# Driver.net
KiCad netlist of a schematic drawn in Altium Designer
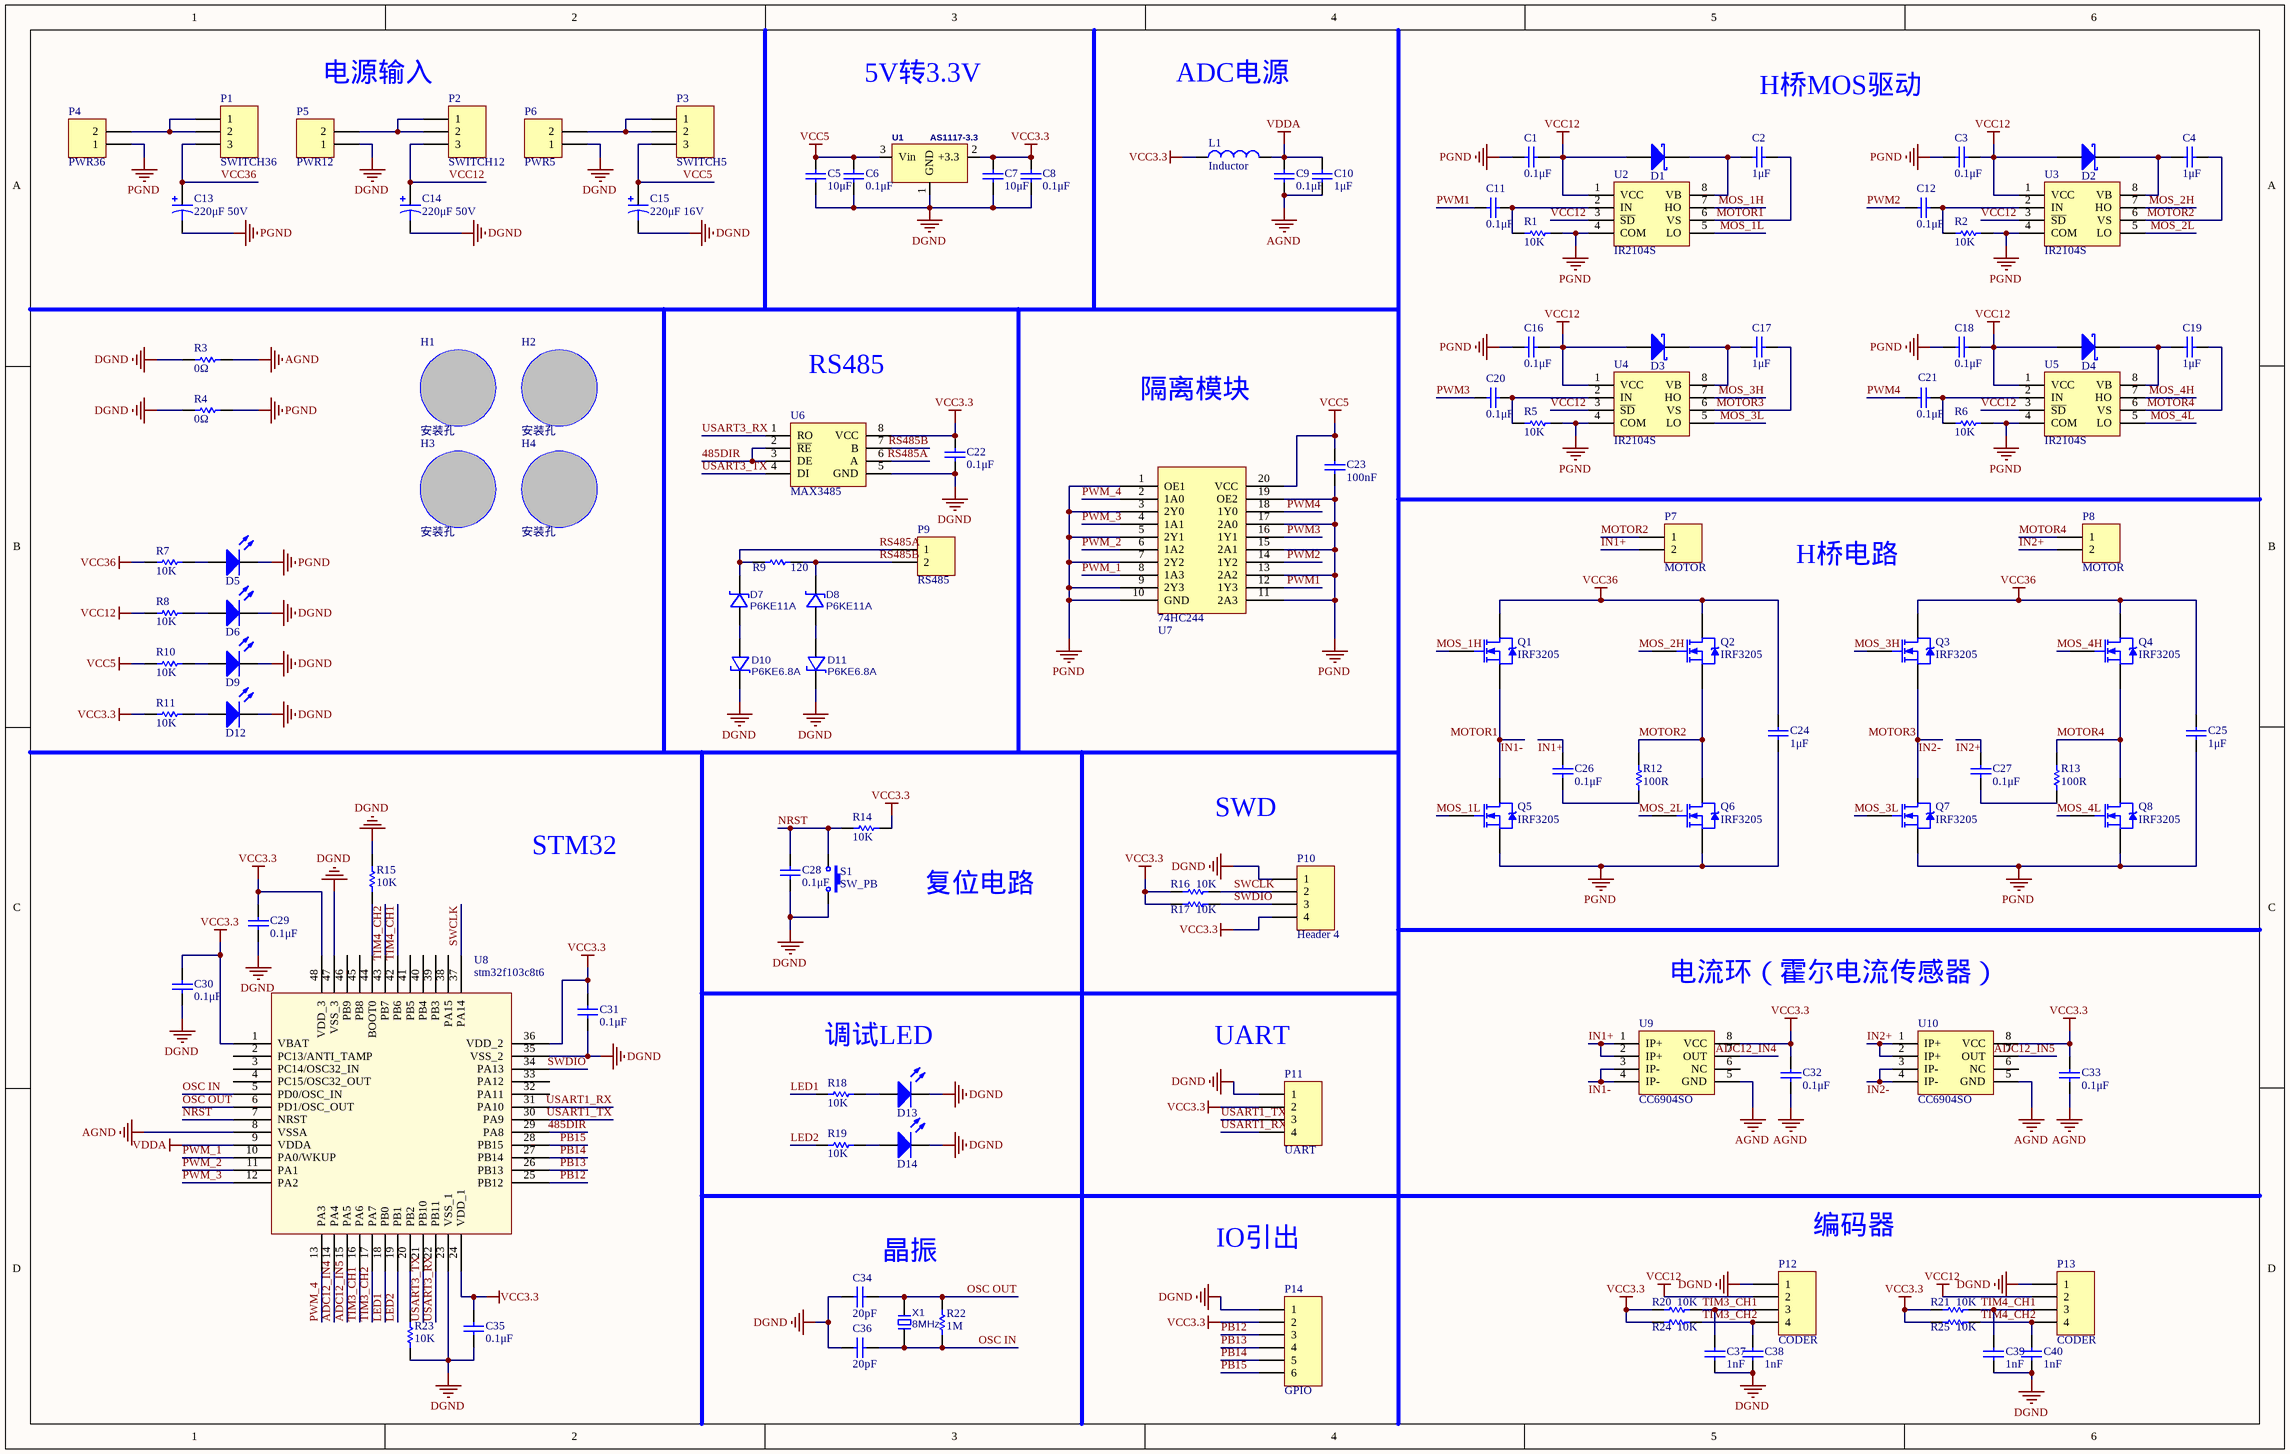
[diagram p0: Driver.SchDoc]

(export (version "E")
  (design (tool "Eeschema 10.0.6"))
  (components
    (comp (ref "C1")
      (value "0.1μF")
      (footprint "0603C")
      (description "Capacitor")
      (fields (field (name "PUBLISHER") "Altium Limited"))
      (libsource (lib "Driver") (part "Cap"))
    )
    (comp (ref "C2")
      (value "1μF")
      (footprint "0603C")
      (description "Capacitor")
      (fields (field (name "PUBLISHER") "Altium Limited"))
      (libsource (lib "Driver") (part "Cap"))
    )
    (comp (ref "C3")
      (value "0.1μF")
      (footprint "0603C")
      (description "Capacitor")
      (fields (field (name "PUBLISHER") "Altium Limited"))
      (libsource (lib "Driver") (part "Cap"))
    )
    (comp (ref "C4")
      (value "1μF")
      (footprint "0603C")
      (description "Capacitor")
      (fields (field (name "PUBLISHER") "Altium Limited"))
      (libsource (lib "Driver") (part "Cap"))
    )
    (comp (ref "C5")
      (value "10μF")
      (footprint "0603C")
      (description "Capacitor")
      (fields (field (name "PUBLISHER") "Altium Limited"))
      (libsource (lib "Driver") (part "Cap"))
    )
    (comp (ref "C6")
      (value "0.1μF")
      (footprint "0603C")
      (description "Capacitor")
      (fields (field (name "PUBLISHER") "Altium Limited"))
      (libsource (lib "Driver") (part "Cap"))
    )
    (comp (ref "C7")
      (value "10μF")
      (footprint "0603C")
      (description "Capacitor")
      (fields (field (name "PUBLISHER") "Altium Limited"))
      (libsource (lib "Driver") (part "Cap"))
    )
    (comp (ref "C8")
      (value "0.1μF")
      (footprint "0603C")
      (description "Capacitor")
      (fields (field (name "PUBLISHER") "Altium Limited"))
      (libsource (lib "Driver") (part "Cap"))
    )
    (comp (ref "C9")
      (value "0.1μF")
      (footprint "0603C")
      (description "Capacitor")
      (fields (field (name "PUBLISHER") "Altium Limited"))
      (libsource (lib "Driver") (part "Cap"))
    )
    (comp (ref "C10")
      (value "1μF")
      (footprint "0603C")
      (description "Capacitor")
      (fields (field (name "PUBLISHER") "Altium Limited"))
      (libsource (lib "Driver") (part "Cap"))
    )
    (comp (ref "C11")
      (value "0.1μF")
      (footprint "0603C")
      (description "Capacitor")
      (fields (field (name "PUBLISHER") "Altium Limited"))
      (libsource (lib "Driver") (part "Cap"))
    )
    (comp (ref "C12")
      (value "0.1μF")
      (footprint "0603C")
      (description "Capacitor")
      (fields (field (name "PUBLISHER") "Altium Limited"))
      (libsource (lib "Driver") (part "Cap"))
    )
    (comp (ref "C13")
      (value "220μF 50V")
      (footprint "CAP-TH_BD10.0-P5.00-D1.0-FD")
      (description "Capacitor")
      (libsource (lib "Driver") (part "Cap_A"))
    )
    (comp (ref "C14")
      (value "220μF 50V")
      (footprint "CAP-TH_BD10.0-P5.00-D1.0-FD")
      (description "Capacitor")
      (libsource (lib "Driver") (part "Cap_A"))
    )
    (comp (ref "C15")
      (value "220μF 16V")
      (footprint "CAP-TH_BD6.3-P2.50-D1.0-FD")
      (description "Capacitor")
      (libsource (lib "Driver") (part "Cap_A"))
    )
    (comp (ref "C16")
      (value "0.1μF")
      (footprint "0603C")
      (description "Capacitor")
      (fields (field (name "PUBLISHER") "Altium Limited"))
      (libsource (lib "Driver") (part "Cap"))
    )
    (comp (ref "C17")
      (value "1μF")
      (footprint "0603C")
      (description "Capacitor")
      (fields (field (name "PUBLISHER") "Altium Limited"))
      (libsource (lib "Driver") (part "Cap"))
    )
    (comp (ref "C18")
      (value "0.1μF")
      (footprint "0603C")
      (description "Capacitor")
      (fields (field (name "PUBLISHER") "Altium Limited"))
      (libsource (lib "Driver") (part "Cap"))
    )
    (comp (ref "C19")
      (value "1μF")
      (footprint "0603C")
      (description "Capacitor")
      (fields (field (name "PUBLISHER") "Altium Limited"))
      (libsource (lib "Driver") (part "Cap"))
    )
    (comp (ref "C20")
      (value "0.1μF")
      (footprint "0603C")
      (description "Capacitor")
      (fields (field (name "PUBLISHER") "Altium Limited"))
      (libsource (lib "Driver") (part "Cap"))
    )
    (comp (ref "C21")
      (value "0.1μF")
      (footprint "0603C")
      (description "Capacitor")
      (fields (field (name "PUBLISHER") "Altium Limited"))
      (libsource (lib "Driver") (part "Cap"))
    )
    (comp (ref "C22")
      (value "0.1μF")
      (footprint "0603C")
      (description "Capacitor")
      (fields (field (name "PUBLISHER") "Altium Limited"))
      (libsource (lib "Driver") (part "Cap"))
    )
    (comp (ref "C23")
      (value "100nF")
      (footprint "0603C")
      (description "Capacitor")
      (fields (field (name "PUBLISHER") "Altium Limited"))
      (libsource (lib "Driver") (part "Cap"))
    )
    (comp (ref "C24")
      (value "1μF")
      (footprint "C1206")
      (description "Capacitor")
      (fields (field (name "PUBLISHER") "Altium Limited"))
      (libsource (lib "Driver") (part "Cap"))
    )
    (comp (ref "C25")
      (value "1μF")
      (footprint "C1206")
      (description "Capacitor")
      (fields (field (name "PUBLISHER") "Altium Limited"))
      (libsource (lib "Driver") (part "Cap"))
    )
    (comp (ref "C26")
      (value "0.1μF")
      (footprint "0603C")
      (description "Capacitor")
      (fields (field (name "PUBLISHER") "Altium Limited"))
      (libsource (lib "Driver") (part "Cap"))
    )
    (comp (ref "C27")
      (value "0.1μF")
      (footprint "0603C")
      (description "Capacitor")
      (fields (field (name "PUBLISHER") "Altium Limited"))
      (libsource (lib "Driver") (part "Cap"))
    )
    (comp (ref "C28")
      (value "0.1μF")
      (footprint "0603C")
      (description "Capacitor")
      (fields (field (name "PUBLISHER") "Altium Limited"))
      (libsource (lib "Driver") (part "Cap"))
    )
    (comp (ref "C29")
      (value "0.1μF")
      (footprint "0603C")
      (description "Capacitor")
      (fields (field (name "PUBLISHER") "Altium Limited"))
      (libsource (lib "Driver") (part "Cap"))
    )
    (comp (ref "C30")
      (value "0.1μF")
      (footprint "0603C")
      (description "Capacitor")
      (fields (field (name "PUBLISHER") "Altium Limited"))
      (libsource (lib "Driver") (part "Cap"))
    )
    (comp (ref "C31")
      (value "0.1μF")
      (footprint "0603C")
      (description "Capacitor")
      (fields (field (name "PUBLISHER") "Altium Limited"))
      (libsource (lib "Driver") (part "Cap"))
    )
    (comp (ref "C32")
      (value "0.1μF")
      (footprint "0603C")
      (description "Capacitor")
      (fields (field (name "PUBLISHER") "Altium Limited"))
      (libsource (lib "Driver") (part "Cap"))
    )
    (comp (ref "C33")
      (value "0.1μF")
      (footprint "0603C")
      (description "Capacitor")
      (fields (field (name "PUBLISHER") "Altium Limited"))
      (libsource (lib "Driver") (part "Cap"))
    )
    (comp (ref "C34")
      (value "20pF")
      (footprint "0603C")
      (description "Capacitor")
      (fields (field (name "PUBLISHER") "Altium Limited"))
      (libsource (lib "Driver") (part "Cap"))
    )
    (comp (ref "C35")
      (value "0.1μF")
      (footprint "0603C")
      (description "Capacitor")
      (fields (field (name "PUBLISHER") "Altium Limited"))
      (libsource (lib "Driver") (part "Cap"))
    )
    (comp (ref "C36")
      (value "20pF")
      (footprint "0603C")
      (description "Capacitor")
      (fields (field (name "PUBLISHER") "Altium Limited"))
      (libsource (lib "Driver") (part "Cap"))
    )
    (comp (ref "C37")
      (value "1nF")
      (footprint "6-0805_N")
      (description "Capacitor")
      (fields (field (name "PUBLISHER") "Altium Limited"))
      (libsource (lib "") (part "Cap_1"))
    )
    (comp (ref "C38")
      (value "1nF")
      (footprint "6-0805_N")
      (description "Capacitor")
      (fields (field (name "PUBLISHER") "Altium Limited"))
      (libsource (lib "") (part "Cap_1"))
    )
    (comp (ref "C39")
      (value "1nF")
      (footprint "6-0805_N")
      (description "Capacitor")
      (fields (field (name "PUBLISHER") "Altium Limited"))
      (libsource (lib "") (part "Cap_1"))
    )
    (comp (ref "C40")
      (value "1nF")
      (footprint "6-0805_N")
      (description "Capacitor")
      (fields (field (name "PUBLISHER") "Altium Limited"))
      (libsource (lib "") (part "Cap_1"))
    )
    (comp (ref "D1")
      (value "D-SS12")
      (footprint "SMA_L4.4-W2.6-LS5.0-RD")
      (libsource (lib "Driver") (part "D-SS12"))
    )
    (comp (ref "D2")
      (value "D-SS12")
      (footprint "SMA_L4.4-W2.6-LS5.0-RD")
      (libsource (lib "Driver") (part "D-SS12"))
    )
    (comp (ref "D3")
      (value "D-SS12")
      (footprint "SMA_L4.4-W2.6-LS5.0-RD")
      (libsource (lib "Driver") (part "D-SS12"))
    )
    (comp (ref "D4")
      (value "D-SS12")
      (footprint "SMA_L4.4-W2.6-LS5.0-RD")
      (libsource (lib "Driver") (part "D-SS12"))
    )
    (comp (ref "D5") (value "LED_0603") (footprint "0603D") (libsource (lib "Driver") (part "LED_0603")))
    (comp (ref "D6") (value "LED_0603") (footprint "0603D") (libsource (lib "Driver") (part "LED_0603")))
    (comp (ref "D7")
      (value "P6KE11A")
      (footprint "SMB")
      (fields (field (name "BOM_MANUFACTURER PART") "P6KE68A") (field (name "BOM_SUPPLIER PART") "C10195"))
      (libsource (lib "Driver") (part "P6KE68A"))
    )
    (comp (ref "D8")
      (value "P6KE11A")
      (footprint "SMB")
      (fields (field (name "BOM_MANUFACTURER PART") "P6KE68A") (field (name "BOM_SUPPLIER PART") "C10195"))
      (libsource (lib "Driver") (part "P6KE68A"))
    )
    (comp (ref "D9") (value "LED_0603") (footprint "0603D") (libsource (lib "Driver") (part "LED_0603")))
    (comp (ref "D10")
      (value "P6KE6.8A")
      (footprint "SMB")
      (fields (field (name "BOM_MANUFACTURER PART") "P6KE68A") (field (name "BOM_SUPPLIER PART") "C10195"))
      (libsource (lib "Driver") (part "P6KE68A"))
    )
    (comp (ref "D11")
      (value "P6KE6.8A")
      (footprint "SMB")
      (fields (field (name "BOM_MANUFACTURER PART") "P6KE68A") (field (name "BOM_SUPPLIER PART") "C10195"))
      (libsource (lib "Driver") (part "P6KE68A"))
    )
    (comp (ref "D12") (value "LED_0603") (footprint "0603D") (libsource (lib "Driver") (part "LED_0603")))
    (comp (ref "D13") (value "LED_0603") (footprint "0603D") (libsource (lib "Driver") (part "LED_0603")))
    (comp (ref "D14") (value "LED_0603") (footprint "0603D") (libsource (lib "Driver") (part "LED_0603")))
    (comp (ref "H1") (value "安装孔") (footprint "安装孔") (libsource (lib "Driver") (part "安装孔")))
    (comp (ref "H2") (value "安装孔") (footprint "安装孔") (libsource (lib "Driver") (part "安装孔")))
    (comp (ref "H3") (value "安装孔") (footprint "安装孔") (libsource (lib "Driver") (part "安装孔")))
    (comp (ref "H4") (value "安装孔") (footprint "安装孔") (libsource (lib "Driver") (part "安装孔")))
    (comp (ref "L1") (value "Inductor") (footprint "0603L") (libsource (lib "Driver") (part "Inductor")))
    (comp (ref "P1")
      (value "SWITCH36")
      (footprint "船型开关")
      (description "Header, 3-Pin")
      (fields (field (name "PUBLISHER") "Altium Limited"))
      (libsource (lib "Miscellaneous Connectors") (part "Header 3"))
    )
    (comp (ref "P2")
      (value "SWITCH12")
      (footprint "钮子开关")
      (description "Header, 3-Pin")
      (fields (field (name "PUBLISHER") "Altium Limited"))
      (libsource (lib "Miscellaneous Connectors") (part "Header 3"))
    )
    (comp (ref "P3")
      (value "SWITCH5")
      (footprint "SWITCH_SS-12F44")
      (description "Header, 3-Pin")
      (fields (field (name "PUBLISHER") "Altium Limited"))
      (libsource (lib "Miscellaneous Connectors") (part "Header 3"))
    )
    (comp (ref "P4")
      (value "PWR36")
      (footprint "KF301")
      (description "Header, 2-Pin")
      (fields (field (name "PUBLISHER") "Altium Limited"))
      (libsource (lib "Miscellaneous Connectors") (part "Header 2"))
    )
    (comp (ref "P5")
      (value "PWR12")
      (footprint "HDR1X2")
      (description "Header, 2-Pin")
      (fields (field (name "PUBLISHER") "Altium Limited"))
      (libsource (lib "Miscellaneous Connectors") (part "Header 2"))
    )
    (comp (ref "P6")
      (value "PWR5")
      (footprint "HDR1X2")
      (description "Header, 2-Pin")
      (fields (field (name "PUBLISHER") "Altium Limited"))
      (libsource (lib "Miscellaneous Connectors") (part "Header 2"))
    )
    (comp (ref "P7")
      (value "MOTOR")
      (footprint "KF301")
      (description "Header, 2-Pin")
      (fields (field (name "PUBLISHER") "Altium Limited"))
      (libsource (lib "") (part "Header 2_1"))
    )
    (comp (ref "P8")
      (value "MOTOR")
      (footprint "KF301")
      (description "Header, 2-Pin")
      (fields (field (name "PUBLISHER") "Altium Limited"))
      (libsource (lib "") (part "Header 2_1"))
    )
    (comp (ref "P9")
      (value "RS485")
      (footprint "HDR1X2")
      (description "Header, 2-Pin")
      (fields (field (name "PUBLISHER") "Altium Limited"))
      (libsource (lib "") (part "Header 2_1"))
    )
    (comp (ref "P10")
      (value "Header 4")
      (footprint "HDR1X4")
      (description "Header, 4-Pin")
      (fields (field (name "PUBLISHER") "Altium Limited"))
      (libsource (lib "Miscellaneous Connectors") (part "Header 4"))
    )
    (comp (ref "P11")
      (value "UART")
      (footprint "HDR1X4")
      (description "Header, 4-Pin")
      (fields (field (name "PUBLISHER") "Altium Limited"))
      (libsource (lib "Miscellaneous Connectors") (part "Header 4"))
    )
    (comp (ref "P12")
      (value "CODER")
      (footprint "HDR1X4")
      (description "Header, 4-Pin")
      (fields (field (name "PUBLISHER") "Altium Limited"))
      (libsource (lib "Miscellaneous Connectors") (part "Header 4"))
    )
    (comp (ref "P13")
      (value "CODER")
      (footprint "HDR1X4")
      (description "Header, 4-Pin")
      (fields (field (name "PUBLISHER") "Altium Limited"))
      (libsource (lib "Miscellaneous Connectors") (part "Header 4"))
    )
    (comp (ref "P14")
      (value "GPIO")
      (footprint "HDR1X6")
      (description "Header, 6-Pin")
      (fields (field (name "PUBLISHER") "Altium Limited"))
      (libsource (lib "Miscellaneous Connectors") (part "Header 6"))
    )
    (comp (ref "Q1")
      (value "IRF3205")
      (footprint "IRF3205_D2PAK")
      (fields (field (name "PUBLISHER") "Altium Limited"))
      (libsource (lib "Driver") (part "IRF3205"))
    )
    (comp (ref "Q2")
      (value "IRF3205")
      (footprint "IRF3205_D2PAK")
      (fields (field (name "PUBLISHER") "Altium Limited"))
      (libsource (lib "Driver") (part "IRF3205"))
    )
    (comp (ref "Q3")
      (value "IRF3205")
      (footprint "IRF3205_D2PAK")
      (fields (field (name "PUBLISHER") "Altium Limited"))
      (libsource (lib "Driver") (part "IRF3205"))
    )
    (comp (ref "Q4")
      (value "IRF3205")
      (footprint "IRF3205_D2PAK")
      (fields (field (name "PUBLISHER") "Altium Limited"))
      (libsource (lib "Driver") (part "IRF3205"))
    )
    (comp (ref "Q5")
      (value "IRF3205")
      (footprint "IRF3205_D2PAK")
      (fields (field (name "PUBLISHER") "Altium Limited"))
      (libsource (lib "Driver") (part "IRF3205"))
    )
    (comp (ref "Q6")
      (value "IRF3205")
      (footprint "IRF3205_D2PAK")
      (fields (field (name "PUBLISHER") "Altium Limited"))
      (libsource (lib "Driver") (part "IRF3205"))
    )
    (comp (ref "Q7")
      (value "IRF3205")
      (footprint "IRF3205_D2PAK")
      (fields (field (name "PUBLISHER") "Altium Limited"))
      (libsource (lib "Driver") (part "IRF3205"))
    )
    (comp (ref "Q8")
      (value "IRF3205")
      (footprint "IRF3205_D2PAK")
      (fields (field (name "PUBLISHER") "Altium Limited"))
      (libsource (lib "Driver") (part "IRF3205"))
    )
    (comp (ref "R1")
      (value "10K")
      (footprint "0603R")
      (description "Resistor")
      (fields (field (name "PUBLISHER") "Altium Limited"))
      (libsource (lib "Driver") (part "Res1"))
    )
    (comp (ref "R2")
      (value "10K")
      (footprint "0603R")
      (description "Resistor")
      (fields (field (name "PUBLISHER") "Altium Limited"))
      (libsource (lib "Driver") (part "Res1"))
    )
    (comp (ref "R3")
      (value "0Ω")
      (footprint "0603R")
      (description "Resistor")
      (fields (field (name "PUBLISHER") "Altium Limited"))
      (libsource (lib "Driver") (part "Res1"))
    )
    (comp (ref "R4")
      (value "0Ω")
      (footprint "0603R")
      (description "Resistor")
      (fields (field (name "PUBLISHER") "Altium Limited"))
      (libsource (lib "Driver") (part "Res1"))
    )
    (comp (ref "R5")
      (value "10K")
      (footprint "0603R")
      (description "Resistor")
      (fields (field (name "PUBLISHER") "Altium Limited"))
      (libsource (lib "Driver") (part "Res1"))
    )
    (comp (ref "R6")
      (value "10K")
      (footprint "0603R")
      (description "Resistor")
      (fields (field (name "PUBLISHER") "Altium Limited"))
      (libsource (lib "Driver") (part "Res1"))
    )
    (comp (ref "R7")
      (value "10K")
      (footprint "0603R")
      (description "Resistor")
      (fields (field (name "PUBLISHER") "Altium Limited"))
      (libsource (lib "Driver") (part "Res1"))
    )
    (comp (ref "R8")
      (value "10K")
      (footprint "0603R")
      (description "Resistor")
      (fields (field (name "PUBLISHER") "Altium Limited"))
      (libsource (lib "Driver") (part "Res1"))
    )
    (comp (ref "R9")
      (value "120")
      (footprint "0603R")
      (description "Resistor")
      (fields (field (name "PUBLISHER") "Altium Limited"))
      (libsource (lib "Driver") (part "Res1"))
    )
    (comp (ref "R10")
      (value "10K")
      (footprint "0603R")
      (description "Resistor")
      (fields (field (name "PUBLISHER") "Altium Limited"))
      (libsource (lib "Driver") (part "Res1"))
    )
    (comp (ref "R11")
      (value "10K")
      (footprint "0603R")
      (description "Resistor")
      (fields (field (name "PUBLISHER") "Altium Limited"))
      (libsource (lib "Driver") (part "Res1"))
    )
    (comp (ref "R12")
      (value "100R")
      (footprint "0603R")
      (description "Resistor")
      (fields (field (name "PUBLISHER") "Altium Limited"))
      (libsource (lib "Driver") (part "Res1"))
    )
    (comp (ref "R13")
      (value "100R")
      (footprint "0603R")
      (description "Resistor")
      (fields (field (name "PUBLISHER") "Altium Limited"))
      (libsource (lib "Driver") (part "Res1"))
    )
    (comp (ref "R14")
      (value "10K")
      (footprint "0603R")
      (description "Resistor")
      (fields (field (name "PUBLISHER") "Altium Limited"))
      (libsource (lib "Driver") (part "Res1"))
    )
    (comp (ref "R15")
      (value "10K")
      (footprint "0603R")
      (description "Resistor")
      (fields (field (name "PUBLISHER") "Altium Limited"))
      (libsource (lib "Driver") (part "Res1"))
    )
    (comp (ref "R16")
      (value "10K")
      (footprint "0603R")
      (description "Resistor")
      (fields (field (name "PUBLISHER") "Altium Limited"))
      (libsource (lib "Driver") (part "Res1"))
    )
    (comp (ref "R17")
      (value "10K")
      (footprint "0603R")
      (description "Resistor")
      (fields (field (name "PUBLISHER") "Altium Limited"))
      (libsource (lib "Driver") (part "Res1"))
    )
    (comp (ref "R18")
      (value "10K")
      (footprint "0603R")
      (description "Resistor")
      (fields (field (name "PUBLISHER") "Altium Limited"))
      (libsource (lib "Driver") (part "Res1"))
    )
    (comp (ref "R19")
      (value "10K")
      (footprint "0603R")
      (description "Resistor")
      (fields (field (name "PUBLISHER") "Altium Limited"))
      (libsource (lib "Driver") (part "Res1"))
    )
    (comp (ref "R20")
      (value "10K")
      (footprint "0603R")
      (description "Resistor")
      (fields (field (name "PUBLISHER") "Altium Limited"))
      (libsource (lib "Driver") (part "Res1"))
    )
    (comp (ref "R21")
      (value "10K")
      (footprint "0603R")
      (description "Resistor")
      (fields (field (name "PUBLISHER") "Altium Limited"))
      (libsource (lib "Driver") (part "Res1"))
    )
    (comp (ref "R22")
      (value "1M")
      (footprint "0603R")
      (description "Resistor")
      (fields (field (name "PUBLISHER") "Altium Limited"))
      (libsource (lib "Driver") (part "Res1"))
    )
    (comp (ref "R23")
      (value "10K")
      (footprint "0603R")
      (description "Resistor")
      (fields (field (name "PUBLISHER") "Altium Limited"))
      (libsource (lib "Driver") (part "Res1"))
    )
    (comp (ref "R24")
      (value "10K")
      (footprint "0603R")
      (description "Resistor")
      (fields (field (name "PUBLISHER") "Altium Limited"))
      (libsource (lib "Driver") (part "Res1"))
    )
    (comp (ref "R25")
      (value "10K")
      (footprint "0603R")
      (description "Resistor")
      (fields (field (name "PUBLISHER") "Altium Limited"))
      (libsource (lib "Driver") (part "Res1"))
    )
    (comp (ref "S1")
      (value "SW_PB")
      (footprint "SMD_6MM*3MM")
      (description "SWITCH")
      (libsource (lib "Driver") (part "SW_PB"))
    )
    (comp (ref "U1")
      (value "AS1117-3.3")
      (footprint "SOT223_N")
      (libsource (lib "Driver") (part "AS1117-3.3"))
    )
    (comp (ref "U2") (value "IR2104S") (footprint "SO8_N") (libsource (lib "Driver") (part "IR2104S")))
    (comp (ref "U3") (value "IR2104S") (footprint "SO8_N") (libsource (lib "Driver") (part "IR2104S")))
    (comp (ref "U4") (value "IR2104S") (footprint "SO8_N") (libsource (lib "Driver") (part "IR2104S")))
    (comp (ref "U5") (value "IR2104S") (footprint "SO8_N") (libsource (lib "Driver") (part "IR2104S")))
    (comp (ref "U6") (value "MAX3485") (footprint "SO8_N") (libsource (lib "Driver") (part "MAX3485")))
    (comp (ref "U7")
      (value "74HC244")
      (footprint "SOIC-20_L13.3-W7.5-P1.27-LS7.8-BL")
      (libsource (lib "Driver") (part "74HC244"))
    )
    (comp (ref "U8")
      (value "stm32f103c8t6")
      (footprint "STM-LQFP48_N")
      (libsource (lib "Driver") (part "stm32f103c8t6"))
    )
    (comp (ref "U9") (value "CC6904SO") (footprint "SO8_N") (libsource (lib "Driver") (part "CC6902SO")))
    (comp (ref "U10") (value "CC6904SO") (footprint "SO8_N") (libsource (lib "Driver") (part "CC6902SO")))
    (comp (ref "X1")
      (value "8MHz")
      (footprint "HC-49US_L11.5-W4.5-P4.88")
      (description "Crystal")
      (fields
        (field (name "BOM_SUPPLIER PART") "C258976")
        (field (name "BOM_MANUFACTURER PART") "B08000J065")
        (field (name "CONTRIBUTOR") "LCSC")
      )
      (libsource (lib "Driver") (part "8MHz"))
    )
  )
  (nets
    (net (code "1") (name "/485DIR") (class "Default")
      (node (ref "U6") (pin "2") (pinfunction "~{RE}_2") (pintype "passive"))
      (node (ref "U6") (pin "3") (pinfunction "DE_3") (pintype "passive"))
      (node (ref "U8") (pin "29") (pinfunction "PA8_29") (pintype "passive"))
    )
    (net (code "2") (name "/ADC12_IN4") (class "Default")
      (node (ref "U8") (pin "14") (pinfunction "PA4_14") (pintype "passive"))
      (node (ref "U9") (pin "7") (pinfunction "OUT_7") (pintype "passive"))
    )
    (net (code "3") (name "/ADC12_IN5") (class "Default")
      (node (ref "U10") (pin "7") (pinfunction "OUT_7") (pintype "passive"))
      (node (ref "U8") (pin "15") (pinfunction "PA5_15") (pintype "passive"))
    )
    (net (code "4") (name "/IN1+") (class "Default")
      (node (ref "C26") (pin "2") (pinfunction "2_2") (pintype "passive"))
      (node (ref "P7") (pin "2") (pinfunction "2_2") (pintype "passive"))
      (node (ref "U9") (pin "1") (pinfunction "IP+_1") (pintype "passive"))
      (node (ref "U9") (pin "2") (pinfunction "IP+_2") (pintype "passive"))
    )
    (net (code "5") (name "/IN1-") (class "Default")
      (node (ref "C2") (pin "2") (pinfunction "2_2") (pintype "passive"))
      (node (ref "Q1") (pin "3") (pinfunction "S_3") (pintype "passive"))
      (node (ref "Q5") (pin "2") (pinfunction "D_2") (pintype "passive"))
      (node (ref "U2") (pin "6") (pinfunction "VS_6") (pintype "passive"))
      (node (ref "U9") (pin "3") (pinfunction "IP-_3") (pintype "passive"))
      (node (ref "U9") (pin "4") (pinfunction "IP-_4") (pintype "passive"))
    )
    (net (code "6") (name "/IN2+") (class "Default")
      (node (ref "C27") (pin "2") (pinfunction "2_2") (pintype "passive"))
      (node (ref "P8") (pin "2") (pinfunction "2_2") (pintype "passive"))
      (node (ref "U10") (pin "1") (pinfunction "IP+_1") (pintype "passive"))
      (node (ref "U10") (pin "2") (pinfunction "IP+_2") (pintype "passive"))
    )
    (net (code "7") (name "/IN2-") (class "Default")
      (node (ref "C17") (pin "2") (pinfunction "2_2") (pintype "passive"))
      (node (ref "Q3") (pin "3") (pinfunction "S_3") (pintype "passive"))
      (node (ref "Q7") (pin "2") (pinfunction "D_2") (pintype "passive"))
      (node (ref "U10") (pin "3") (pinfunction "IP-_3") (pintype "passive"))
      (node (ref "U10") (pin "4") (pinfunction "IP-_4") (pintype "passive"))
      (node (ref "U4") (pin "6") (pinfunction "VS_6") (pintype "passive"))
    )
    (net (code "8") (name "/LED1") (class "Default")
      (node (ref "R18") (pin "2") (pinfunction "2_2") (pintype "passive"))
      (node (ref "U8") (pin "18") (pinfunction "PB0_18") (pintype "passive"))
    )
    (net (code "9") (name "/LED2") (class "Default")
      (node (ref "R19") (pin "2") (pinfunction "2_2") (pintype "passive"))
      (node (ref "U8") (pin "19") (pinfunction "PB1_19") (pintype "passive"))
    )
    (net (code "10") (name "/MOS_1H") (class "Default")
      (node (ref "Q1") (pin "1") (pinfunction "G_1") (pintype "passive"))
      (node (ref "U2") (pin "7") (pinfunction "HO_7") (pintype "passive"))
    )
    (net (code "11") (name "/MOS_1L") (class "Default")
      (node (ref "Q5") (pin "1") (pinfunction "G_1") (pintype "passive"))
      (node (ref "U2") (pin "5") (pinfunction "LO_5") (pintype "passive"))
    )
    (net (code "12") (name "/MOS_2H") (class "Default")
      (node (ref "Q2") (pin "1") (pinfunction "G_1") (pintype "passive"))
      (node (ref "U3") (pin "7") (pinfunction "HO_7") (pintype "passive"))
    )
    (net (code "13") (name "/MOS_2L") (class "Default")
      (node (ref "Q6") (pin "1") (pinfunction "G_1") (pintype "passive"))
      (node (ref "U3") (pin "5") (pinfunction "LO_5") (pintype "passive"))
    )
    (net (code "14") (name "/MOS_3H") (class "Default")
      (node (ref "Q3") (pin "1") (pinfunction "G_1") (pintype "passive"))
      (node (ref "U4") (pin "7") (pinfunction "HO_7") (pintype "passive"))
    )
    (net (code "15") (name "/MOS_3L") (class "Default")
      (node (ref "Q7") (pin "1") (pinfunction "G_1") (pintype "passive"))
      (node (ref "U4") (pin "5") (pinfunction "LO_5") (pintype "passive"))
    )
    (net (code "16") (name "/MOS_4H") (class "Default")
      (node (ref "Q4") (pin "1") (pinfunction "G_1") (pintype "passive"))
      (node (ref "U5") (pin "7") (pinfunction "HO_7") (pintype "passive"))
    )
    (net (code "17") (name "/MOS_4L") (class "Default")
      (node (ref "Q8") (pin "1") (pinfunction "G_1") (pintype "passive"))
      (node (ref "U5") (pin "5") (pinfunction "LO_5") (pintype "passive"))
    )
    (net (code "18") (name "/MOTOR2") (class "Default")
      (node (ref "C4") (pin "2") (pinfunction "2_2") (pintype "passive"))
      (node (ref "P7") (pin "1") (pinfunction "1_1") (pintype "passive"))
      (node (ref "Q2") (pin "3") (pinfunction "S_3") (pintype "passive"))
      (node (ref "Q6") (pin "2") (pinfunction "D_2") (pintype "passive"))
      (node (ref "R12") (pin "2") (pinfunction "2_2") (pintype "passive"))
      (node (ref "U3") (pin "6") (pinfunction "VS_6") (pintype "passive"))
    )
    (net (code "19") (name "/MOTOR4") (class "Default")
      (node (ref "C19") (pin "2") (pinfunction "2_2") (pintype "passive"))
      (node (ref "P8") (pin "1") (pinfunction "1_1") (pintype "passive"))
      (node (ref "Q4") (pin "3") (pinfunction "S_3") (pintype "passive"))
      (node (ref "Q8") (pin "2") (pinfunction "D_2") (pintype "passive"))
      (node (ref "R13") (pin "2") (pinfunction "2_2") (pintype "passive"))
      (node (ref "U5") (pin "6") (pinfunction "VS_6") (pintype "passive"))
    )
    (net (code "20") (name "/NRST") (class "Default")
      (node (ref "C28") (pin "2") (pinfunction "2_2") (pintype "passive"))
      (node (ref "R14") (pin "2") (pinfunction "2_2") (pintype "passive"))
      (node (ref "S1") (pin "1") (pinfunction "1_1") (pintype "passive"))
      (node (ref "U8") (pin "7") (pinfunction "NRST_7") (pintype "passive"))
    )
    (net (code "21") (name "/OSC IN") (class "Default")
      (node (ref "C36") (pin "1") (pinfunction "1_1") (pintype "passive"))
      (node (ref "R22") (pin "2") (pinfunction "2_2") (pintype "passive"))
      (node (ref "U8") (pin "5") (pinfunction "PD0/OSC_IN_5") (pintype "passive"))
      (node (ref "X1") (pin "1") (pinfunction "1_1") (pintype "passive"))
    )
    (net (code "22") (name "/OSC OUT") (class "Default")
      (node (ref "C34") (pin "1") (pinfunction "1_1") (pintype "passive"))
      (node (ref "R22") (pin "1") (pinfunction "1_1") (pintype "passive"))
      (node (ref "U8") (pin "6") (pinfunction "PD1/OSC_OUT_6") (pintype "passive"))
      (node (ref "X1") (pin "2") (pinfunction "2_2") (pintype "passive"))
    )
    (net (code "23") (name "/PB12") (class "Default")
      (node (ref "P14") (pin "3") (pinfunction "3_3") (pintype "passive"))
      (node (ref "U8") (pin "25") (pinfunction "PB12_25") (pintype "passive"))
    )
    (net (code "24") (name "/PB13") (class "Default")
      (node (ref "P14") (pin "4") (pinfunction "4_4") (pintype "passive"))
      (node (ref "U8") (pin "26") (pinfunction "PB13_26") (pintype "passive"))
    )
    (net (code "25") (name "/PB14") (class "Default")
      (node (ref "P14") (pin "5") (pinfunction "5_5") (pintype "passive"))
      (node (ref "U8") (pin "27") (pinfunction "PB14_27") (pintype "passive"))
    )
    (net (code "26") (name "/PB15") (class "Default")
      (node (ref "P14") (pin "6") (pinfunction "6_6") (pintype "passive"))
      (node (ref "U8") (pin "28") (pinfunction "PB15_28") (pintype "passive"))
    )
    (net (code "27") (name "/PWM1") (class "Default")
      (node (ref "C11") (pin "1") (pinfunction "1_1") (pintype "passive"))
      (node (ref "U7") (pin "12") (pinfunction "1Y3_12") (pintype "passive"))
    )
    (net (code "28") (name "/PWM2") (class "Default")
      (node (ref "C12") (pin "1") (pinfunction "1_1") (pintype "passive"))
      (node (ref "U7") (pin "14") (pinfunction "1Y2_14") (pintype "passive"))
    )
    (net (code "29") (name "/PWM3") (class "Default")
      (node (ref "C20") (pin "1") (pinfunction "1_1") (pintype "passive"))
      (node (ref "U7") (pin "16") (pinfunction "1Y1_16") (pintype "passive"))
    )
    (net (code "30") (name "/PWM4") (class "Default")
      (node (ref "C21") (pin "1") (pinfunction "1_1") (pintype "passive"))
      (node (ref "U7") (pin "18") (pinfunction "1Y0_18") (pintype "passive"))
    )
    (net (code "31") (name "/PWM_1") (class "Default")
      (node (ref "U7") (pin "8") (pinfunction "1A3_8") (pintype "passive"))
      (node (ref "U8") (pin "10") (pinfunction "PA0/WKUP_10") (pintype "passive"))
    )
    (net (code "32") (name "/PWM_2") (class "Default")
      (node (ref "U7") (pin "6") (pinfunction "1A2_6") (pintype "passive"))
      (node (ref "U8") (pin "11") (pinfunction "PA1_11") (pintype "passive"))
    )
    (net (code "33") (name "/PWM_3") (class "Default")
      (node (ref "U7") (pin "4") (pinfunction "1A1_4") (pintype "passive"))
      (node (ref "U8") (pin "12") (pinfunction "PA2_12") (pintype "passive"))
    )
    (net (code "34") (name "/PWM_4") (class "Default")
      (node (ref "U7") (pin "2") (pinfunction "1A0_2") (pintype "passive"))
      (node (ref "U8") (pin "13") (pinfunction "PA3_13") (pintype "passive"))
    )
    (net (code "35") (name "/RS485A") (class "Default")
      (node (ref "D7") (pin "2") (pinfunction "K_2") (pintype "passive"))
      (node (ref "P9") (pin "1") (pinfunction "1_1") (pintype "passive"))
      (node (ref "R9") (pin "1") (pinfunction "1_1") (pintype "passive"))
      (node (ref "U6") (pin "6") (pinfunction "A_6") (pintype "passive"))
    )
    (net (code "36") (name "/RS485B") (class "Default")
      (node (ref "D8") (pin "2") (pinfunction "K_2") (pintype "passive"))
      (node (ref "P9") (pin "2") (pinfunction "2_2") (pintype "passive"))
      (node (ref "R9") (pin "2") (pinfunction "2_2") (pintype "passive"))
      (node (ref "U6") (pin "7") (pinfunction "B_7") (pintype "passive"))
    )
    (net (code "37") (name "/SWCLK") (class "Default")
      (node (ref "P10") (pin "2") (pinfunction "2_2") (pintype "passive"))
      (node (ref "R16") (pin "2") (pinfunction "2_2") (pintype "passive"))
      (node (ref "U8") (pin "37") (pinfunction "PA14_37") (pintype "passive"))
    )
    (net (code "38") (name "/SWDIO") (class "Default")
      (node (ref "P10") (pin "3") (pinfunction "3_3") (pintype "passive"))
      (node (ref "R17") (pin "2") (pinfunction "2_2") (pintype "passive"))
      (node (ref "U8") (pin "34") (pinfunction "PA13_34") (pintype "passive"))
    )
    (net (code "39") (name "/TIM3_CH1") (class "Default")
      (node (ref "C37") (pin "2") (pinfunction "2_2") (pintype "passive"))
      (node (ref "P12") (pin "3") (pinfunction "3_3") (pintype "passive"))
      (node (ref "R20") (pin "1") (pinfunction "1_1") (pintype "passive"))
      (node (ref "U8") (pin "16") (pinfunction "PA6_16") (pintype "passive"))
    )
    (net (code "40") (name "/TIM3_CH2") (class "Default")
      (node (ref "C38") (pin "2") (pinfunction "2_2") (pintype "passive"))
      (node (ref "P12") (pin "4") (pinfunction "4_4") (pintype "passive"))
      (node (ref "R24") (pin "1") (pinfunction "1_1") (pintype "passive"))
      (node (ref "U8") (pin "17") (pinfunction "PA7_17") (pintype "passive"))
    )
    (net (code "41") (name "/TIM4_CH1") (class "Default")
      (node (ref "C39") (pin "2") (pinfunction "2_2") (pintype "passive"))
      (node (ref "P13") (pin "3") (pinfunction "3_3") (pintype "passive"))
      (node (ref "R21") (pin "1") (pinfunction "1_1") (pintype "passive"))
      (node (ref "U8") (pin "42") (pinfunction "PB6_42") (pintype "passive"))
    )
    (net (code "42") (name "/TIM4_CH2") (class "Default")
      (node (ref "C40") (pin "2") (pinfunction "2_2") (pintype "passive"))
      (node (ref "P13") (pin "4") (pinfunction "4_4") (pintype "passive"))
      (node (ref "R25") (pin "1") (pinfunction "1_1") (pintype "passive"))
      (node (ref "U8") (pin "43") (pinfunction "PB7_43") (pintype "passive"))
    )
    (net (code "43") (name "/USART1_RX") (class "Default")
      (node (ref "P11") (pin "4") (pinfunction "4_4") (pintype "passive"))
      (node (ref "U8") (pin "31") (pinfunction "PA10_31") (pintype "passive"))
    )
    (net (code "44") (name "/USART1_TX") (class "Default")
      (node (ref "P11") (pin "3") (pinfunction "3_3") (pintype "passive"))
      (node (ref "U8") (pin "30") (pinfunction "PA9_30") (pintype "passive"))
    )
    (net (code "45") (name "/USART3_RX") (class "Default")
      (node (ref "U6") (pin "1") (pinfunction "RO_1") (pintype "passive"))
      (node (ref "U8") (pin "22") (pinfunction "PB11_22") (pintype "passive"))
    )
    (net (code "46") (name "/USART3_TX") (class "Default")
      (node (ref "U6") (pin "4") (pinfunction "DI_4") (pintype "passive"))
      (node (ref "U8") (pin "21") (pinfunction "PB10_21") (pintype "passive"))
    )
    (net (code "47") (name "AGND") (class "Default")
      (node (ref "C10") (pin "1") (pinfunction "1_1") (pintype "passive"))
      (node (ref "C32") (pin "1") (pinfunction "1_1") (pintype "passive"))
      (node (ref "C33") (pin "1") (pinfunction "1_1") (pintype "passive"))
      (node (ref "C9") (pin "1") (pinfunction "1_1") (pintype "passive"))
      (node (ref "R3") (pin "1") (pinfunction "1_1") (pintype "passive"))
      (node (ref "U10") (pin "5") (pinfunction "GND_5") (pintype "passive"))
      (node (ref "U8") (pin "8") (pinfunction "VSSA_8") (pintype "passive"))
      (node (ref "U9") (pin "5") (pinfunction "GND_5") (pintype "passive"))
    )
    (net (code "48") (name "DGND") (class "Default")
      (node (ref "C14") (pin "2") (pinfunction "2_2") (pintype "passive"))
      (node (ref "C15") (pin "2") (pinfunction "2_2") (pintype "passive"))
      (node (ref "C22") (pin "2") (pinfunction "2_2") (pintype "passive"))
      (node (ref "C28") (pin "1") (pinfunction "1_1") (pintype "passive"))
      (node (ref "C29") (pin "1") (pinfunction "1_1") (pintype "passive"))
      (node (ref "C30") (pin "1") (pinfunction "1_1") (pintype "passive"))
      (node (ref "C31") (pin "1") (pinfunction "1_1") (pintype "passive"))
      (node (ref "C34") (pin "2") (pinfunction "2_2") (pintype "passive"))
      (node (ref "C35") (pin "1") (pinfunction "1_1") (pintype "passive"))
      (node (ref "C36") (pin "2") (pinfunction "2_2") (pintype "passive"))
      (node (ref "C37") (pin "1") (pinfunction "1_1") (pintype "passive"))
      (node (ref "C38") (pin "1") (pinfunction "1_1") (pintype "passive"))
      (node (ref "C39") (pin "1") (pinfunction "1_1") (pintype "passive"))
      (node (ref "C40") (pin "1") (pinfunction "1_1") (pintype "passive"))
      (node (ref "C5") (pin "1") (pinfunction "1_1") (pintype "passive"))
      (node (ref "C6") (pin "1") (pinfunction "1_1") (pintype "passive"))
      (node (ref "C7") (pin "1") (pinfunction "1_1") (pintype "passive"))
      (node (ref "C8") (pin "1") (pinfunction "1_1") (pintype "passive"))
      (node (ref "D10") (pin "2") (pinfunction "K_2") (pintype "passive"))
      (node (ref "D11") (pin "2") (pinfunction "K_2") (pintype "passive"))
      (node (ref "D12") (pin "2") (pinfunction "K_2") (pintype "passive"))
      (node (ref "D13") (pin "2") (pinfunction "K_2") (pintype "passive"))
      (node (ref "D14") (pin "2") (pinfunction "K_2") (pintype "passive"))
      (node (ref "D6") (pin "2") (pinfunction "K_2") (pintype "passive"))
      (node (ref "D9") (pin "2") (pinfunction "K_2") (pintype "passive"))
      (node (ref "P10") (pin "1") (pinfunction "1_1") (pintype "passive"))
      (node (ref "P11") (pin "1") (pinfunction "1_1") (pintype "passive"))
      (node (ref "P12") (pin "1") (pinfunction "1_1") (pintype "passive"))
      (node (ref "P13") (pin "1") (pinfunction "1_1") (pintype "passive"))
      (node (ref "P14") (pin "1") (pinfunction "1_1") (pintype "passive"))
      (node (ref "P5") (pin "1") (pinfunction "1_1") (pintype "passive"))
      (node (ref "P6") (pin "1") (pinfunction "1_1") (pintype "passive"))
      (node (ref "R15") (pin "1") (pinfunction "1_1") (pintype "passive"))
      (node (ref "R23") (pin "2") (pinfunction "2_2") (pintype "passive"))
      (node (ref "R3") (pin "2") (pinfunction "2_2") (pintype "passive"))
      (node (ref "R4") (pin "2") (pinfunction "2_2") (pintype "passive"))
      (node (ref "S1") (pin "2") (pinfunction "2_2") (pintype "passive"))
      (node (ref "U1") (pin "1") (pinfunction "GND_1") (pintype "passive"))
      (node (ref "U6") (pin "5") (pinfunction "GND_5") (pintype "passive"))
      (node (ref "U8") (pin "23") (pinfunction "VSS_1_23") (pintype "passive"))
      (node (ref "U8") (pin "35") (pinfunction "VSS_2_35") (pintype "passive"))
      (node (ref "U8") (pin "47") (pinfunction "VSS_3_47") (pintype "passive"))
    )
    (net (code "49") (name "Net-(C26-Pad1)") (class "Default")
      (node (ref "C26") (pin "1") (pinfunction "1_1") (pintype "passive"))
      (node (ref "R12") (pin "1") (pinfunction "1_1") (pintype "passive"))
    )
    (net (code "50") (name "Net-(C27-Pad1)") (class "Default")
      (node (ref "C27") (pin "1") (pinfunction "1_1") (pintype "passive"))
      (node (ref "R13") (pin "1") (pinfunction "1_1") (pintype "passive"))
    )
    (net (code "51") (name "Net-(D1-K)") (class "Default")
      (node (ref "C2") (pin "1") (pinfunction "1_1") (pintype "passive"))
      (node (ref "D1") (pin "2") (pinfunction "K_2") (pintype "passive"))
      (node (ref "U2") (pin "8") (pinfunction "VB_8") (pintype "passive"))
    )
    (net (code "52") (name "Net-(D2-K)") (class "Default")
      (node (ref "C4") (pin "1") (pinfunction "1_1") (pintype "passive"))
      (node (ref "D2") (pin "2") (pinfunction "K_2") (pintype "passive"))
      (node (ref "U3") (pin "8") (pinfunction "VB_8") (pintype "passive"))
    )
    (net (code "53") (name "Net-(D3-K)") (class "Default")
      (node (ref "C17") (pin "1") (pinfunction "1_1") (pintype "passive"))
      (node (ref "D3") (pin "2") (pinfunction "K_2") (pintype "passive"))
      (node (ref "U4") (pin "8") (pinfunction "VB_8") (pintype "passive"))
    )
    (net (code "54") (name "Net-(D4-K)") (class "Default")
      (node (ref "C19") (pin "1") (pinfunction "1_1") (pintype "passive"))
      (node (ref "D4") (pin "2") (pinfunction "K_2") (pintype "passive"))
      (node (ref "U5") (pin "8") (pinfunction "VB_8") (pintype "passive"))
    )
    (net (code "55") (name "Net-(D5-A)") (class "Default")
      (node (ref "D5") (pin "1") (pinfunction "A_1") (pintype "passive"))
      (node (ref "R7") (pin "1") (pinfunction "1_1") (pintype "passive"))
    )
    (net (code "56") (name "Net-(D6-A)") (class "Default")
      (node (ref "D6") (pin "1") (pinfunction "A_1") (pintype "passive"))
      (node (ref "R8") (pin "1") (pinfunction "1_1") (pintype "passive"))
    )
    (net (code "57") (name "Net-(D9-A)") (class "Default")
      (node (ref "D9") (pin "1") (pinfunction "A_1") (pintype "passive"))
      (node (ref "R10") (pin "1") (pinfunction "1_1") (pintype "passive"))
    )
    (net (code "58") (name "Net-(D10-A)") (class "Default")
      (node (ref "D10") (pin "1") (pinfunction "A_1") (pintype "passive"))
      (node (ref "D7") (pin "1") (pinfunction "A_1") (pintype "passive"))
    )
    (net (code "59") (name "Net-(D11-A)") (class "Default")
      (node (ref "D11") (pin "1") (pinfunction "A_1") (pintype "passive"))
      (node (ref "D8") (pin "1") (pinfunction "A_1") (pintype "passive"))
    )
    (net (code "60") (name "Net-(D12-A)") (class "Default")
      (node (ref "D12") (pin "1") (pinfunction "A_1") (pintype "passive"))
      (node (ref "R11") (pin "1") (pinfunction "1_1") (pintype "passive"))
    )
    (net (code "61") (name "Net-(D13-A)") (class "Default")
      (node (ref "D13") (pin "1") (pinfunction "A_1") (pintype "passive"))
      (node (ref "R18") (pin "1") (pinfunction "1_1") (pintype "passive"))
    )
    (net (code "62") (name "Net-(D14-A)") (class "Default")
      (node (ref "D14") (pin "1") (pinfunction "A_1") (pintype "passive"))
      (node (ref "R19") (pin "1") (pinfunction "1_1") (pintype "passive"))
    )
    (net (code "63") (name "Net-(P1-Pad1)") (class "Default")
      (node (ref "P1") (pin "1") (pinfunction "1_1") (pintype "passive"))
      (node (ref "P1") (pin "2") (pinfunction "2_2") (pintype "passive"))
      (node (ref "P4") (pin "2") (pinfunction "2_2") (pintype "passive"))
    )
    (net (code "64") (name "Net-(P2-Pad1)") (class "Default")
      (node (ref "P2") (pin "1") (pinfunction "1_1") (pintype "passive"))
      (node (ref "P2") (pin "2") (pinfunction "2_2") (pintype "passive"))
      (node (ref "P5") (pin "2") (pinfunction "2_2") (pintype "passive"))
    )
    (net (code "65") (name "Net-(P3-Pad1)") (class "Default")
      (node (ref "P3") (pin "1") (pinfunction "1_1") (pintype "passive"))
      (node (ref "P3") (pin "2") (pinfunction "2_2") (pintype "passive"))
      (node (ref "P6") (pin "2") (pinfunction "2_2") (pintype "passive"))
    )
    (net (code "66") (name "Net-(U2-IN)") (class "Default")
      (node (ref "C11") (pin "2") (pinfunction "2_2") (pintype "passive"))
      (node (ref "R1") (pin "2") (pinfunction "2_2") (pintype "passive"))
      (node (ref "U2") (pin "2") (pinfunction "IN_2") (pintype "passive"))
    )
    (net (code "67") (name "Net-(U3-IN)") (class "Default")
      (node (ref "C12") (pin "2") (pinfunction "2_2") (pintype "passive"))
      (node (ref "R2") (pin "2") (pinfunction "2_2") (pintype "passive"))
      (node (ref "U3") (pin "2") (pinfunction "IN_2") (pintype "passive"))
    )
    (net (code "68") (name "Net-(U4-IN)") (class "Default")
      (node (ref "C20") (pin "2") (pinfunction "2_2") (pintype "passive"))
      (node (ref "R5") (pin "2") (pinfunction "2_2") (pintype "passive"))
      (node (ref "U4") (pin "2") (pinfunction "IN_2") (pintype "passive"))
    )
    (net (code "69") (name "Net-(U5-IN)") (class "Default")
      (node (ref "C21") (pin "2") (pinfunction "2_2") (pintype "passive"))
      (node (ref "R6") (pin "2") (pinfunction "2_2") (pintype "passive"))
      (node (ref "U5") (pin "2") (pinfunction "IN_2") (pintype "passive"))
    )
    (net (code "70") (name "Net-(U8-BOOT0)") (class "Default")
      (node (ref "R15") (pin "2") (pinfunction "2_2") (pintype "passive"))
      (node (ref "U8") (pin "44") (pinfunction "BOOT0_44") (pintype "passive"))
    )
    (net (code "71") (name "Net-(U8-PB2)") (class "Default")
      (node (ref "R23") (pin "1") (pinfunction "1_1") (pintype "passive"))
      (node (ref "U8") (pin "20") (pinfunction "PB2_20") (pintype "passive"))
    )
    (net (code "72") (name "PGND") (class "Default")
      (node (ref "C1") (pin "1") (pinfunction "1_1") (pintype "passive"))
      (node (ref "C13") (pin "2") (pinfunction "2_2") (pintype "passive"))
      (node (ref "C16") (pin "1") (pinfunction "1_1") (pintype "passive"))
      (node (ref "C18") (pin "1") (pinfunction "1_1") (pintype "passive"))
      (node (ref "C23") (pin "2") (pinfunction "2_2") (pintype "passive"))
      (node (ref "C24") (pin "1") (pinfunction "1_1") (pintype "passive"))
      (node (ref "C25") (pin "1") (pinfunction "1_1") (pintype "passive"))
      (node (ref "C3") (pin "1") (pinfunction "1_1") (pintype "passive"))
      (node (ref "D5") (pin "2") (pinfunction "K_2") (pintype "passive"))
      (node (ref "P4") (pin "1") (pinfunction "1_1") (pintype "passive"))
      (node (ref "Q5") (pin "3") (pinfunction "S_3") (pintype "passive"))
      (node (ref "Q6") (pin "3") (pinfunction "S_3") (pintype "passive"))
      (node (ref "Q7") (pin "3") (pinfunction "S_3") (pintype "passive"))
      (node (ref "Q8") (pin "3") (pinfunction "S_3") (pintype "passive"))
      (node (ref "R1") (pin "1") (pinfunction "1_1") (pintype "passive"))
      (node (ref "R2") (pin "1") (pinfunction "1_1") (pintype "passive"))
      (node (ref "R4") (pin "1") (pinfunction "1_1") (pintype "passive"))
      (node (ref "R5") (pin "1") (pinfunction "1_1") (pintype "passive"))
      (node (ref "R6") (pin "1") (pinfunction "1_1") (pintype "passive"))
      (node (ref "U2") (pin "4") (pinfunction "COM_4") (pintype "passive"))
      (node (ref "U3") (pin "4") (pinfunction "COM_4") (pintype "passive"))
      (node (ref "U4") (pin "4") (pinfunction "COM_4") (pintype "passive"))
      (node (ref "U5") (pin "4") (pinfunction "COM_4") (pintype "passive"))
      (node (ref "U7") (pin "1") (pinfunction "OE1_1") (pintype "passive"))
      (node (ref "U7") (pin "10") (pinfunction "GND_10") (pintype "passive"))
      (node (ref "U7") (pin "11") (pinfunction "2A3_11") (pintype "passive"))
      (node (ref "U7") (pin "13") (pinfunction "2A2_13") (pintype "passive"))
      (node (ref "U7") (pin "15") (pinfunction "2A1_15") (pintype "passive"))
      (node (ref "U7") (pin "17") (pinfunction "2A0_17") (pintype "passive"))
      (node (ref "U7") (pin "19") (pinfunction "OE2_19") (pintype "passive"))
      (node (ref "U7") (pin "3") (pinfunction "2Y0_3") (pintype "passive"))
      (node (ref "U7") (pin "5") (pinfunction "2Y1_5") (pintype "passive"))
      (node (ref "U7") (pin "7") (pinfunction "2Y2_7") (pintype "passive"))
      (node (ref "U7") (pin "9") (pinfunction "2Y3_9") (pintype "passive"))
    )
    (net (code "73") (name "VCC3.3") (class "Default")
      (node (ref "C22") (pin "1") (pinfunction "1_1") (pintype "passive"))
      (node (ref "C29") (pin "2") (pinfunction "2_2") (pintype "passive"))
      (node (ref "C30") (pin "2") (pinfunction "2_2") (pintype "passive"))
      (node (ref "C31") (pin "2") (pinfunction "2_2") (pintype "passive"))
      (node (ref "C32") (pin "2") (pinfunction "2_2") (pintype "passive"))
      (node (ref "C33") (pin "2") (pinfunction "2_2") (pintype "passive"))
      (node (ref "C35") (pin "2") (pinfunction "2_2") (pintype "passive"))
      (node (ref "C7") (pin "2") (pinfunction "2_2") (pintype "passive"))
      (node (ref "C8") (pin "2") (pinfunction "2_2") (pintype "passive"))
      (node (ref "L1") (pin "1") (pinfunction "1_1") (pintype "passive"))
      (node (ref "P10") (pin "4") (pinfunction "4_4") (pintype "passive"))
      (node (ref "P11") (pin "2") (pinfunction "2_2") (pintype "passive"))
      (node (ref "P14") (pin "2") (pinfunction "2_2") (pintype "passive"))
      (node (ref "R11") (pin "2") (pinfunction "2_2") (pintype "passive"))
      (node (ref "R14") (pin "1") (pinfunction "1_1") (pintype "passive"))
      (node (ref "R16") (pin "1") (pinfunction "1_1") (pintype "passive"))
      (node (ref "R17") (pin "1") (pinfunction "1_1") (pintype "passive"))
      (node (ref "R20") (pin "2") (pinfunction "2_2") (pintype "passive"))
      (node (ref "R21") (pin "2") (pinfunction "2_2") (pintype "passive"))
      (node (ref "R24") (pin "2") (pinfunction "2_2") (pintype "passive"))
      (node (ref "R25") (pin "2") (pinfunction "2_2") (pintype "passive"))
      (node (ref "U1") (pin "2") (pinfunction "+3.3_2") (pintype "passive"))
      (node (ref "U10") (pin "8") (pinfunction "VCC_8") (pintype "passive"))
      (node (ref "U6") (pin "8") (pinfunction "VCC_8") (pintype "passive"))
      (node (ref "U8") (pin "1") (pinfunction "VBAT_1") (pintype "passive"))
      (node (ref "U8") (pin "24") (pinfunction "VDD_1_24") (pintype "passive"))
      (node (ref "U8") (pin "36") (pinfunction "VDD_2_36") (pintype "passive"))
      (node (ref "U8") (pin "48") (pinfunction "VDD_3_48") (pintype "passive"))
      (node (ref "U9") (pin "8") (pinfunction "VCC_8") (pintype "passive"))
    )
    (net (code "74") (name "VCC5") (class "Default")
      (node (ref "C15") (pin "1") (pinfunction "1_1") (pintype "passive"))
      (node (ref "C23") (pin "1") (pinfunction "1_1") (pintype "passive"))
      (node (ref "C5") (pin "2") (pinfunction "2_2") (pintype "passive"))
      (node (ref "C6") (pin "2") (pinfunction "2_2") (pintype "passive"))
      (node (ref "P3") (pin "3") (pinfunction "3_3") (pintype "passive"))
      (node (ref "R10") (pin "2") (pinfunction "2_2") (pintype "passive"))
      (node (ref "U1") (pin "3") (pinfunction "Vin_3") (pintype "passive"))
      (node (ref "U7") (pin "20") (pinfunction "VCC_20") (pintype "passive"))
    )
    (net (code "75") (name "VCC12") (class "Default")
      (node (ref "C1") (pin "2") (pinfunction "2_2") (pintype "passive"))
      (node (ref "C14") (pin "1") (pinfunction "1_1") (pintype "passive"))
      (node (ref "C16") (pin "2") (pinfunction "2_2") (pintype "passive"))
      (node (ref "C18") (pin "2") (pinfunction "2_2") (pintype "passive"))
      (node (ref "C3") (pin "2") (pinfunction "2_2") (pintype "passive"))
      (node (ref "D1") (pin "1") (pinfunction "A_1") (pintype "passive"))
      (node (ref "D2") (pin "1") (pinfunction "A_1") (pintype "passive"))
      (node (ref "D3") (pin "1") (pinfunction "A_1") (pintype "passive"))
      (node (ref "D4") (pin "1") (pinfunction "A_1") (pintype "passive"))
      (node (ref "P12") (pin "2") (pinfunction "2_2") (pintype "passive"))
      (node (ref "P13") (pin "2") (pinfunction "2_2") (pintype "passive"))
      (node (ref "P2") (pin "3") (pinfunction "3_3") (pintype "passive"))
      (node (ref "R8") (pin "2") (pinfunction "2_2") (pintype "passive"))
      (node (ref "U2") (pin "1") (pinfunction "VCC_1") (pintype "passive"))
      (node (ref "U2") (pin "3") (pinfunction "~{SD}_3") (pintype "passive"))
      (node (ref "U3") (pin "1") (pinfunction "VCC_1") (pintype "passive"))
      (node (ref "U3") (pin "3") (pinfunction "~{SD}_3") (pintype "passive"))
      (node (ref "U4") (pin "1") (pinfunction "VCC_1") (pintype "passive"))
      (node (ref "U4") (pin "3") (pinfunction "~{SD}_3") (pintype "passive"))
      (node (ref "U5") (pin "1") (pinfunction "VCC_1") (pintype "passive"))
      (node (ref "U5") (pin "3") (pinfunction "~{SD}_3") (pintype "passive"))
    )
    (net (code "76") (name "VCC36") (class "Default")
      (node (ref "C13") (pin "1") (pinfunction "1_1") (pintype "passive"))
      (node (ref "C24") (pin "2") (pinfunction "2_2") (pintype "passive"))
      (node (ref "C25") (pin "2") (pinfunction "2_2") (pintype "passive"))
      (node (ref "P1") (pin "3") (pinfunction "3_3") (pintype "passive"))
      (node (ref "Q1") (pin "2") (pinfunction "D_2") (pintype "passive"))
      (node (ref "Q2") (pin "2") (pinfunction "D_2") (pintype "passive"))
      (node (ref "Q3") (pin "2") (pinfunction "D_2") (pintype "passive"))
      (node (ref "Q4") (pin "2") (pinfunction "D_2") (pintype "passive"))
      (node (ref "R7") (pin "2") (pinfunction "2_2") (pintype "passive"))
    )
    (net (code "77") (name "VDDA") (class "Default")
      (node (ref "C10") (pin "2") (pinfunction "2_2") (pintype "passive"))
      (node (ref "C9") (pin "2") (pinfunction "2_2") (pintype "passive"))
      (node (ref "L1") (pin "2") (pinfunction "2_2") (pintype "passive"))
      (node (ref "U8") (pin "9") (pinfunction "VDDA_9") (pintype "passive"))
    )
    (net (code "78") (name "unconnected-(U8-PA11-Pad32)") (class "Default")
      (node (ref "U8") (pin "32") (pinfunction "PA11_32") (pintype "passive"))
    )
    (net (code "79") (name "unconnected-(U8-PA12-Pad33)") (class "Default")
      (node (ref "U8") (pin "33") (pinfunction "PA12_33") (pintype "passive"))
    )
    (net (code "80") (name "unconnected-(U8-PA15-Pad38)") (class "Default")
      (node (ref "U8") (pin "38") (pinfunction "PA15_38") (pintype "passive"))
    )
    (net (code "81") (name "unconnected-(U8-PB3-Pad39)") (class "Default")
      (node (ref "U8") (pin "39") (pinfunction "PB3_39") (pintype "passive"))
    )
    (net (code "82") (name "unconnected-(U8-PB4-Pad40)") (class "Default")
      (node (ref "U8") (pin "40") (pinfunction "PB4_40") (pintype "passive"))
    )
    (net (code "83") (name "unconnected-(U8-PB5-Pad41)") (class "Default")
      (node (ref "U8") (pin "41") (pinfunction "PB5_41") (pintype "passive"))
    )
    (net (code "84") (name "unconnected-(U8-PB8-Pad45)") (class "Default")
      (node (ref "U8") (pin "45") (pinfunction "PB8_45") (pintype "passive"))
    )
    (net (code "85") (name "unconnected-(U8-PB9-Pad46)") (class "Default")
      (node (ref "U8") (pin "46") (pinfunction "PB9_46") (pintype "passive"))
    )
    (net (code "86") (name "unconnected-(U8-PC13{slash}ANTI_TAMP-Pad2)") (class "Default")
      (node (ref "U8") (pin "2") (pinfunction "PC13/ANTI_TAMP_2") (pintype "passive"))
    )
    (net (code "87") (name "unconnected-(U8-PC14{slash}OSC32_IN-Pad3)") (class "Default")
      (node (ref "U8") (pin "3") (pinfunction "PC14/OSC32_IN_3") (pintype "passive"))
    )
    (net (code "88") (name "unconnected-(U8-PC15{slash}OSC32_OUT-Pad4)") (class "Default")
      (node (ref "U8") (pin "4") (pinfunction "PC15/OSC32_OUT_4") (pintype "passive"))
    )
    (net (code "89") (name "unconnected-(U9-NC-Pad6)") (class "Default")
      (node (ref "U9") (pin "6") (pinfunction "NC_6") (pintype "passive"))
    )
    (net (code "90") (name "unconnected-(U10-NC-Pad6)") (class "Default")
      (node (ref "U10") (pin "6") (pinfunction "NC_6") (pintype "passive"))
    )
  )
)
